# TrinketProtoShield.net
KiCad netlist of a schematic drawn in EAGLE
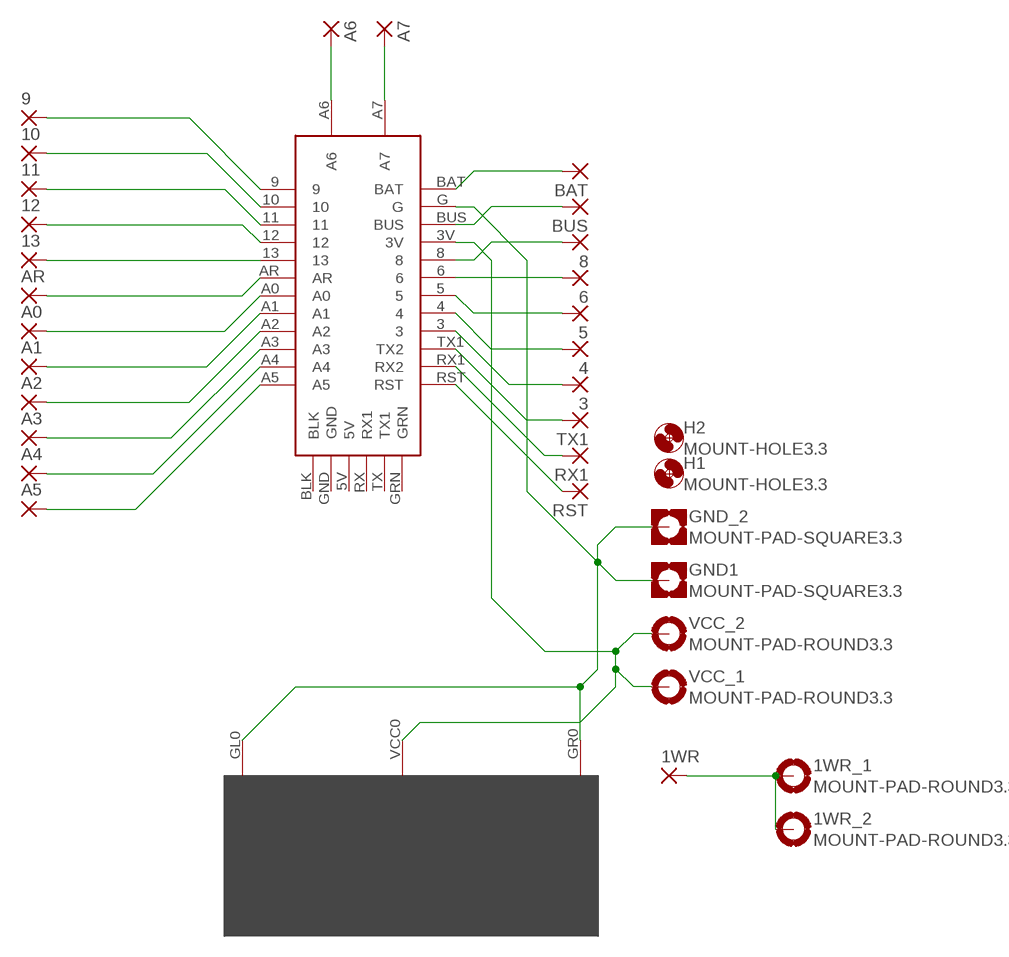
[diagram p0: schematic, sheet 1]

(export (version "E")
  (design (tool "Eeschema 10.0.6"))
  (components
    (comp (ref "1WR")
      (value "1,6/0,9")
      (footprint "eagle-import:1,6_0,9")
      (libsource (lib "eagle-import") (part "1,6/0,9"))
    )
    (comp (ref "1WR_1")
      (value "MOUNT-PAD-ROUND3.3")
      (footprint "eagle-import:3,3-PAD")
      (libsource (lib "eagle-import") (part "MOUNT-PAD-ROUND3.3"))
    )
    (comp (ref "1WR_2")
      (value "MOUNT-PAD-ROUND3.3")
      (footprint "eagle-import:3,3-PAD")
      (libsource (lib "eagle-import") (part "MOUNT-PAD-ROUND3.3"))
    )
    (comp (ref "3")
      (value "1,6/0,9")
      (footprint "eagle-import:1,6_0,9")
      (libsource (lib "eagle-import") (part "1,6/0,9"))
    )
    (comp (ref "4")
      (value "1,6/0,9")
      (footprint "eagle-import:1,6_0,9")
      (libsource (lib "eagle-import") (part "1,6/0,9"))
    )
    (comp (ref "5")
      (value "1,6/0,9")
      (footprint "eagle-import:1,6_0,9")
      (libsource (lib "eagle-import") (part "1,6/0,9"))
    )
    (comp (ref "6")
      (value "1,6/0,9")
      (footprint "eagle-import:1,6_0,9")
      (libsource (lib "eagle-import") (part "1,6/0,9"))
    )
    (comp (ref "8")
      (value "1,6/0,9")
      (footprint "eagle-import:1,6_0,9")
      (libsource (lib "eagle-import") (part "1,6/0,9"))
    )
    (comp (ref "9")
      (value "1,6/0,9")
      (footprint "eagle-import:1,6_0,9")
      (libsource (lib "eagle-import") (part "1,6/0,9"))
    )
    (comp (ref "10")
      (value "1,6/0,9")
      (footprint "eagle-import:1,6_0,9")
      (libsource (lib "eagle-import") (part "1,6/0,9"))
    )
    (comp (ref "11")
      (value "1,6/0,9")
      (footprint "eagle-import:1,6_0,9")
      (libsource (lib "eagle-import") (part "1,6/0,9"))
    )
    (comp (ref "12")
      (value "1,6/0,9")
      (footprint "eagle-import:1,6_0,9")
      (libsource (lib "eagle-import") (part "1,6/0,9"))
    )
    (comp (ref "13")
      (value "1,6/0,9")
      (footprint "eagle-import:1,6_0,9")
      (libsource (lib "eagle-import") (part "1,6/0,9"))
    )
    (comp (ref "A0")
      (value "1,6/0,9")
      (footprint "eagle-import:1,6_0,9")
      (libsource (lib "eagle-import") (part "1,6/0,9"))
    )
    (comp (ref "A1")
      (value "1,6/0,9")
      (footprint "eagle-import:1,6_0,9")
      (libsource (lib "eagle-import") (part "1,6/0,9"))
    )
    (comp (ref "A2")
      (value "1,6/0,9")
      (footprint "eagle-import:1,6_0,9")
      (libsource (lib "eagle-import") (part "1,6/0,9"))
    )
    (comp (ref "A3")
      (value "1,6/0,9")
      (footprint "eagle-import:1,6_0,9")
      (libsource (lib "eagle-import") (part "1,6/0,9"))
    )
    (comp (ref "A4")
      (value "1,6/0,9")
      (footprint "eagle-import:1,6_0,9")
      (libsource (lib "eagle-import") (part "1,6/0,9"))
    )
    (comp (ref "A5")
      (value "1,6/0,9")
      (footprint "eagle-import:1,6_0,9")
      (libsource (lib "eagle-import") (part "1,6/0,9"))
    )
    (comp (ref "A6")
      (value "1,6/0,9")
      (footprint "eagle-import:1,6_0,9")
      (libsource (lib "eagle-import") (part "1,6/0,9"))
    )
    (comp (ref "A7")
      (value "1,6/0,9")
      (footprint "eagle-import:1,6_0,9")
      (libsource (lib "eagle-import") (part "1,6/0,9"))
    )
    (comp (ref "AR")
      (value "1,6/0,9")
      (footprint "eagle-import:1,6_0,9")
      (libsource (lib "eagle-import") (part "1,6/0,9"))
    )
    (comp (ref "BAT")
      (value "1,6/0,9")
      (footprint "eagle-import:1,6_0,9")
      (libsource (lib "eagle-import") (part "1,6/0,9"))
    )
    (comp (ref "BUS")
      (value "1,6/0,9")
      (footprint "eagle-import:1,6_0,9")
      (libsource (lib "eagle-import") (part "1,6/0,9"))
    )
    (comp (ref "GND1")
      (value "MOUNT-PAD-SQUARE3.3")
      (footprint "eagle-import:3,3-PAD-SQUARE")
      (libsource (lib "eagle-import") (part "MOUNT-PAD-SQUARE3.3"))
    )
    (comp (ref "GND_2")
      (value "MOUNT-PAD-SQUARE3.3")
      (footprint "eagle-import:3,3-PAD-SQUARE")
      (libsource (lib "eagle-import") (part "MOUNT-PAD-SQUARE3.3"))
    )
    (comp (ref "H1")
      (value "MOUNT-HOLE3.3")
      (footprint "eagle-import:3,3")
      (libsource (lib "eagle-import") (part "MOUNT-HOLE3.3"))
    )
    (comp (ref "H2")
      (value "MOUNT-HOLE3.3")
      (footprint "eagle-import:3,3")
      (libsource (lib "eagle-import") (part "MOUNT-HOLE3.3"))
    )
    (comp (ref "RST")
      (value "1,6/0,9")
      (footprint "eagle-import:1,6_0,9")
      (libsource (lib "eagle-import") (part "1,6/0,9"))
    )
    (comp (ref "RX1")
      (value "1,6/0,9")
      (footprint "eagle-import:1,6_0,9")
      (libsource (lib "eagle-import") (part "1,6/0,9"))
    )
    (comp (ref "TX1")
      (value "1,6/0,9")
      (footprint "eagle-import:1,6_0,9")
      (libsource (lib "eagle-import") (part "1,6/0,9"))
    )
    (comp (ref "U$1")
      (value "ARDUINO_PRO_TRINKET")
      (footprint "eagle-import:ARDUINO_PRO_TRINKET")
      (libsource (lib "eagle-import") (part "ARDUINO_PRO_TRINKET"))
    )
    (comp (ref "U$2")
      (value "PROTOAREA")
      (footprint "eagle-import:PROTOAREA")
      (libsource (lib "eagle-import") (part "PROTOAREA"))
    )
    (comp (ref "VCC_1")
      (value "MOUNT-PAD-ROUND3.3")
      (footprint "eagle-import:3,3-PAD")
      (libsource (lib "eagle-import") (part "MOUNT-PAD-ROUND3.3"))
    )
    (comp (ref "VCC_2")
      (value "MOUNT-PAD-ROUND3.3")
      (footprint "eagle-import:3,3-PAD")
      (libsource (lib "eagle-import") (part "MOUNT-PAD-ROUND3.3"))
    )
  )
  (nets
    (net (code "1") (name "Net-(1WR-P)") (class "Default")
      (node (ref "1WR") (pin "1") (pinfunction "P_1") (pintype "passive"))
      (node (ref "1WR_1") (pin "B3,3") (pinfunction "MOUNT_B3,3") (pintype "passive"))
      (node (ref "1WR_2") (pin "B3,3") (pinfunction "MOUNT_B3,3") (pintype "passive"))
    )
    (net (code "2") (name "Net-(3-P)") (class "Default")
      (node (ref "3") (pin "1") (pinfunction "P_1") (pintype "passive"))
      (node (ref "U$1") (pin "3") (pinfunction "3_3") (pintype "bidirectional"))
    )
    (net (code "3") (name "Net-(4-P)") (class "Default")
      (node (ref "4") (pin "1") (pinfunction "P_1") (pintype "passive"))
      (node (ref "U$1") (pin "4") (pinfunction "4_4") (pintype "bidirectional"))
    )
    (net (code "4") (name "Net-(5-P)") (class "Default")
      (node (ref "5") (pin "1") (pinfunction "P_1") (pintype "passive"))
      (node (ref "U$1") (pin "5") (pinfunction "5_5") (pintype "bidirectional"))
    )
    (net (code "5") (name "Net-(6-P)") (class "Default")
      (node (ref "6") (pin "1") (pinfunction "P_1") (pintype "passive"))
      (node (ref "U$1") (pin "6") (pinfunction "6_6") (pintype "bidirectional"))
    )
    (net (code "6") (name "Net-(8-P)") (class "Default")
      (node (ref "8") (pin "1") (pinfunction "P_1") (pintype "passive"))
      (node (ref "U$1") (pin "8") (pinfunction "8_8") (pintype "bidirectional"))
    )
    (net (code "7") (name "Net-(9-P)") (class "Default")
      (node (ref "9") (pin "1") (pinfunction "P_1") (pintype "passive"))
      (node (ref "U$1") (pin "9") (pinfunction "9_9") (pintype "bidirectional"))
    )
    (net (code "8") (name "Net-(10-P)") (class "Default")
      (node (ref "10") (pin "1") (pinfunction "P_1") (pintype "passive"))
      (node (ref "U$1") (pin "10") (pinfunction "10_10") (pintype "bidirectional"))
    )
    (net (code "9") (name "Net-(11-P)") (class "Default")
      (node (ref "11") (pin "1") (pinfunction "P_1") (pintype "passive"))
      (node (ref "U$1") (pin "11") (pinfunction "11_11") (pintype "bidirectional"))
    )
    (net (code "10") (name "Net-(12-P)") (class "Default")
      (node (ref "12") (pin "1") (pinfunction "P_1") (pintype "passive"))
      (node (ref "U$1") (pin "12") (pinfunction "12_12") (pintype "bidirectional"))
    )
    (net (code "11") (name "Net-(13-P)") (class "Default")
      (node (ref "13") (pin "1") (pinfunction "P_1") (pintype "passive"))
      (node (ref "U$1") (pin "13") (pinfunction "13_13") (pintype "bidirectional"))
    )
    (net (code "12") (name "Net-(A0-P)") (class "Default")
      (node (ref "A0") (pin "1") (pinfunction "P_1") (pintype "passive"))
      (node (ref "U$1") (pin "A0") (pinfunction "A0_A0") (pintype "bidirectional"))
    )
    (net (code "13") (name "Net-(A1-P)") (class "Default")
      (node (ref "A1") (pin "1") (pinfunction "P_1") (pintype "passive"))
      (node (ref "U$1") (pin "A1") (pinfunction "A1_A1") (pintype "bidirectional"))
    )
    (net (code "14") (name "Net-(A2-P)") (class "Default")
      (node (ref "A2") (pin "1") (pinfunction "P_1") (pintype "passive"))
      (node (ref "U$1") (pin "A2") (pinfunction "A2_A2") (pintype "bidirectional"))
    )
    (net (code "15") (name "Net-(A3-P)") (class "Default")
      (node (ref "A3") (pin "1") (pinfunction "P_1") (pintype "passive"))
      (node (ref "U$1") (pin "A3") (pinfunction "A3_A3") (pintype "bidirectional"))
    )
    (net (code "16") (name "Net-(A4-P)") (class "Default")
      (node (ref "A4") (pin "1") (pinfunction "P_1") (pintype "passive"))
      (node (ref "U$1") (pin "A4") (pinfunction "A4_A4") (pintype "bidirectional"))
    )
    (net (code "17") (name "Net-(A5-P)") (class "Default")
      (node (ref "A5") (pin "1") (pinfunction "P_1") (pintype "passive"))
      (node (ref "U$1") (pin "A5") (pinfunction "A5_A5") (pintype "bidirectional"))
    )
    (net (code "18") (name "Net-(A6-P)") (class "Default")
      (node (ref "A6") (pin "1") (pinfunction "P_1") (pintype "passive"))
      (node (ref "U$1") (pin "A6") (pinfunction "A6_A6") (pintype "bidirectional"))
    )
    (net (code "19") (name "Net-(A7-P)") (class "Default")
      (node (ref "A7") (pin "1") (pinfunction "P_1") (pintype "passive"))
      (node (ref "U$1") (pin "A7") (pinfunction "A7_A7") (pintype "bidirectional"))
    )
    (net (code "20") (name "Net-(AR-P)") (class "Default")
      (node (ref "AR") (pin "1") (pinfunction "P_1") (pintype "passive"))
      (node (ref "U$1") (pin "AR") (pinfunction "AR_AR") (pintype "bidirectional"))
    )
    (net (code "21") (name "Net-(BAT-P)") (class "Default")
      (node (ref "BAT") (pin "1") (pinfunction "P_1") (pintype "passive"))
      (node (ref "U$1") (pin "BAT") (pinfunction "BAT_BAT") (pintype "bidirectional"))
    )
    (net (code "22") (name "Net-(BUS-P)") (class "Default")
      (node (ref "BUS") (pin "1") (pinfunction "P_1") (pintype "passive"))
      (node (ref "U$1") (pin "BUS") (pinfunction "BUS_BUS") (pintype "bidirectional"))
    )
    (net (code "23") (name "Net-(GND1-MOUNT)") (class "Default")
      (node (ref "GND1") (pin "B3,3") (pinfunction "MOUNT_B3,3") (pintype "passive"))
      (node (ref "GND_2") (pin "B3,3") (pinfunction "MOUNT_B3,3") (pintype "passive"))
      (node (ref "U$1") (pin "G") (pinfunction "G_G") (pintype "bidirectional"))
      (node (ref "U$2") (pin "GL0") (pinfunction "RAIL1_GL0") (pintype "bidirectional"))
      (node (ref "U$2") (pin "GR0") (pinfunction "RAIL3_GR0") (pintype "bidirectional"))
    )
    (net (code "24") (name "Net-(RST-P)") (class "Default")
      (node (ref "RST") (pin "1") (pinfunction "P_1") (pintype "passive"))
      (node (ref "U$1") (pin "RST") (pinfunction "RST_RST") (pintype "bidirectional"))
    )
    (net (code "25") (name "Net-(RX1-P)") (class "Default")
      (node (ref "RX1") (pin "1") (pinfunction "P_1") (pintype "passive"))
      (node (ref "U$1") (pin "RX1") (pinfunction "RX2_RX1") (pintype "bidirectional"))
    )
    (net (code "26") (name "Net-(TX1-P)") (class "Default")
      (node (ref "TX1") (pin "1") (pinfunction "P_1") (pintype "passive"))
      (node (ref "U$1") (pin "TX1") (pinfunction "TX2_TX1") (pintype "bidirectional"))
    )
    (net (code "27") (name "Net-(U$2-RAIL2)") (class "Default")
      (node (ref "U$1") (pin "3V") (pinfunction "3V_3V") (pintype "bidirectional"))
      (node (ref "U$2") (pin "VCC0") (pinfunction "RAIL2_VCC0") (pintype "bidirectional"))
      (node (ref "VCC_1") (pin "B3,3") (pinfunction "MOUNT_B3,3") (pintype "passive"))
      (node (ref "VCC_2") (pin "B3,3") (pinfunction "MOUNT_B3,3") (pintype "passive"))
    )
    (net (code "28") (name "unconnected-(U$1-Pad5V)") (class "Default")
      (node (ref "U$1") (pin "5V") (pinfunction "5V_5V") (pintype "bidirectional"))
    )
    (net (code "29") (name "unconnected-(U$1-PadBLK)") (class "Default")
      (node (ref "U$1") (pin "BLK") (pinfunction "BLK_BLK") (pintype "bidirectional"))
    )
    (net (code "30") (name "unconnected-(U$1-PadGND)") (class "Default")
      (node (ref "U$1") (pin "GND") (pinfunction "GND_GND") (pintype "bidirectional"))
    )
    (net (code "31") (name "unconnected-(U$1-PadGRN)") (class "Default")
      (node (ref "U$1") (pin "GRN") (pinfunction "GRN_GRN") (pintype "bidirectional"))
    )
    (net (code "32") (name "unconnected-(U$1-RX1-PadRX)") (class "Default")
      (node (ref "U$1") (pin "RX") (pinfunction "RX1_RX") (pintype "bidirectional"))
    )
    (net (code "33") (name "unconnected-(U$1-TX1-PadTX)") (class "Default")
      (node (ref "U$1") (pin "TX") (pinfunction "TX1_TX") (pintype "bidirectional"))
    )
  )
)
